# LEDs_PUSH_BUTTONS.net
KiCad netlist of a schematic drawn in Altium Designer
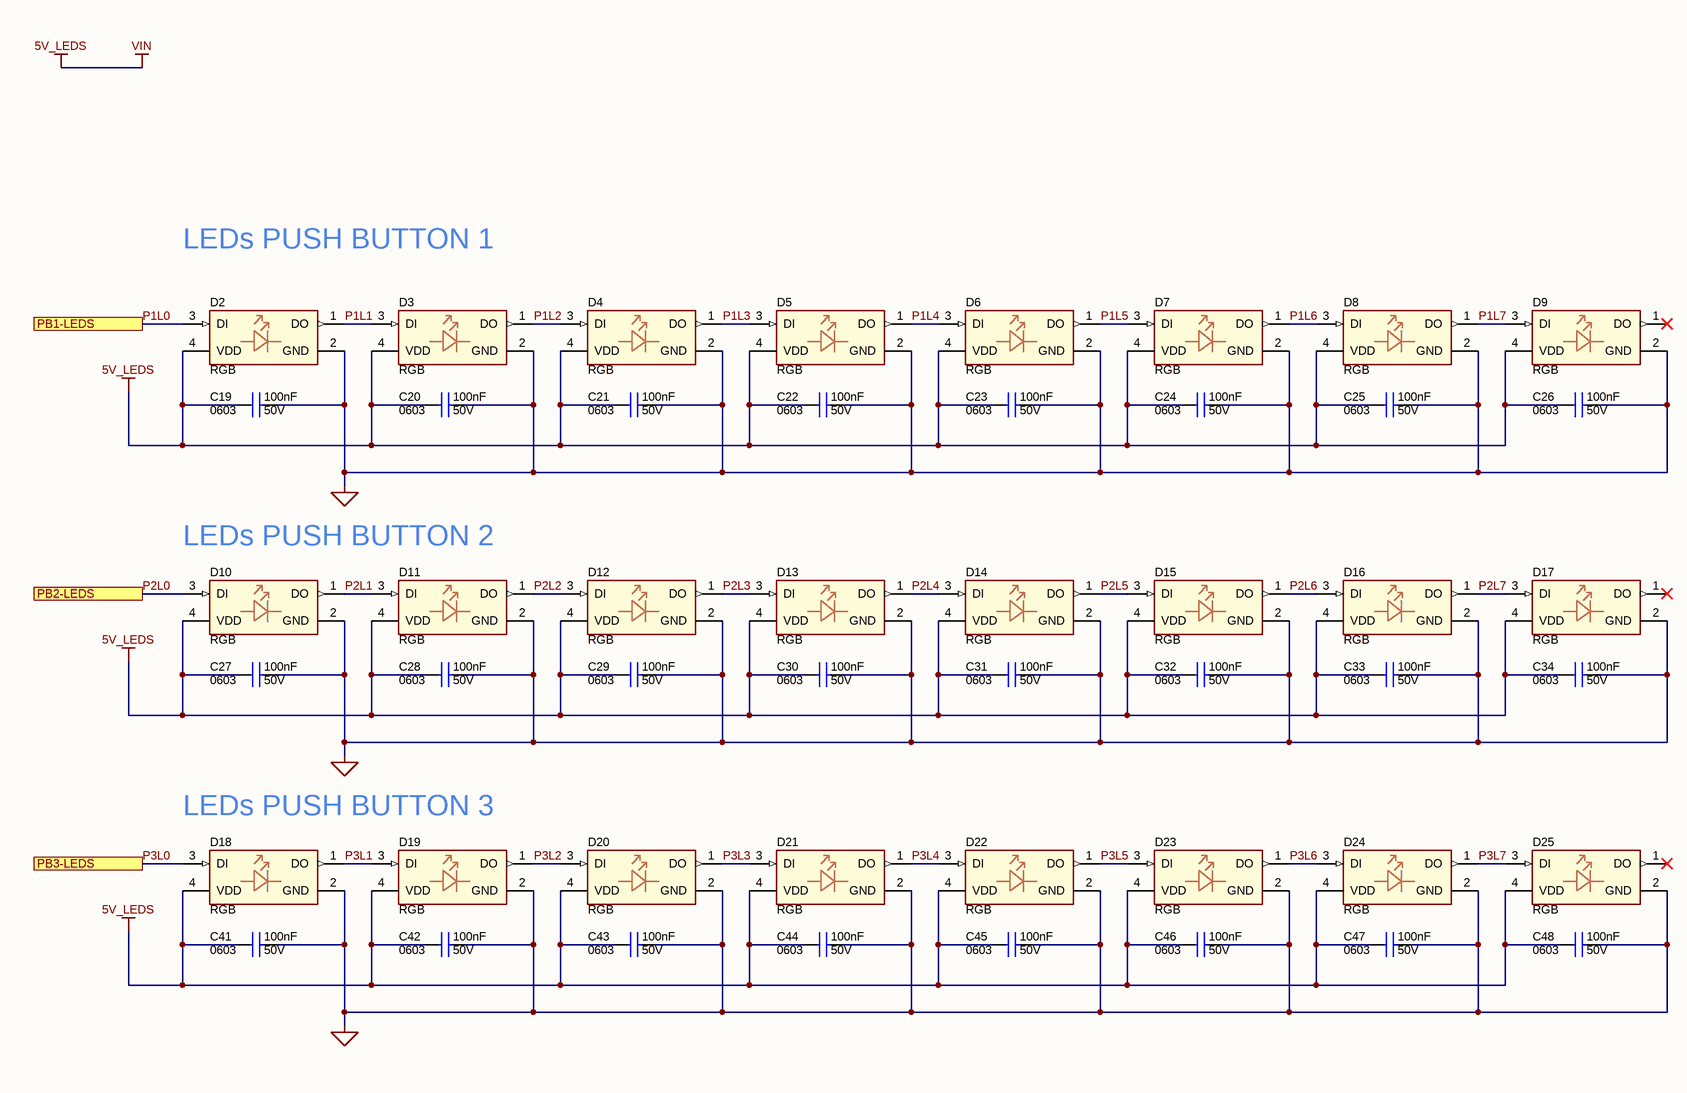
[diagram p0: LEDs PUSH BUTTONS.SchDoc]

(export (version "E")
  (design (tool "Eeschema 10.0.6"))
  (components
    (comp (ref "C19")
      (value "100nF")
      (footprint "CAPC0603X37L")
      (description "CAPACITOR 100 nF 0603 X7R 50V 10%")
      (fields
        (field (name "VOLTAGE") "50V")
        (field (name "MANUFACTURER 1 PART NUMBER") "C0603C104K5RACTU")
        (field (name "TOLERANCE") "10%")
        (field (name "CASE/PACKAGE") "0603")
        (field (name "COMMENT DESIGNER") "can be substituted same values other manufacturer")
      )
      (libsource (lib "EDATRON Solutions GmbH") (part "C"))
    )
    (comp (ref "C20")
      (value "100nF")
      (footprint "CAPC0603X37L")
      (description "CAPACITOR 100 nF 0603 X7R 50V 10%")
      (fields
        (field (name "VOLTAGE") "50V")
        (field (name "MANUFACTURER 1 PART NUMBER") "C0603C104K5RACTU")
        (field (name "TOLERANCE") "10%")
        (field (name "CASE/PACKAGE") "0603")
        (field (name "COMMENT DESIGNER") "can be substituted same values other manufacturer")
      )
      (libsource (lib "EDATRON Solutions GmbH") (part "C"))
    )
    (comp (ref "C21")
      (value "100nF")
      (footprint "CAPC0603X37L")
      (description "CAPACITOR 100 nF 0603 X7R 50V 10%")
      (fields
        (field (name "VOLTAGE") "50V")
        (field (name "MANUFACTURER 1 PART NUMBER") "C0603C104K5RACTU")
        (field (name "TOLERANCE") "10%")
        (field (name "CASE/PACKAGE") "0603")
        (field (name "COMMENT DESIGNER") "can be substituted same values other manufacturer")
      )
      (libsource (lib "EDATRON Solutions GmbH") (part "C"))
    )
    (comp (ref "C22")
      (value "100nF")
      (footprint "CAPC0603X37L")
      (description "CAPACITOR 100 nF 0603 X7R 50V 10%")
      (fields
        (field (name "VOLTAGE") "50V")
        (field (name "MANUFACTURER 1 PART NUMBER") "C0603C104K5RACTU")
        (field (name "TOLERANCE") "10%")
        (field (name "CASE/PACKAGE") "0603")
        (field (name "COMMENT DESIGNER") "can be substituted same values other manufacturer")
      )
      (libsource (lib "EDATRON Solutions GmbH") (part "C"))
    )
    (comp (ref "C23")
      (value "100nF")
      (footprint "CAPC0603X37L")
      (description "CAPACITOR 100 nF 0603 X7R 50V 10%")
      (fields
        (field (name "VOLTAGE") "50V")
        (field (name "MANUFACTURER 1 PART NUMBER") "C0603C104K5RACTU")
        (field (name "TOLERANCE") "10%")
        (field (name "CASE/PACKAGE") "0603")
        (field (name "COMMENT DESIGNER") "can be substituted same values other manufacturer")
      )
      (libsource (lib "EDATRON Solutions GmbH") (part "C"))
    )
    (comp (ref "C24")
      (value "100nF")
      (footprint "CAPC0603X37L")
      (description "CAPACITOR 100 nF 0603 X7R 50V 10%")
      (fields
        (field (name "VOLTAGE") "50V")
        (field (name "MANUFACTURER 1 PART NUMBER") "C0603C104K5RACTU")
        (field (name "TOLERANCE") "10%")
        (field (name "CASE/PACKAGE") "0603")
        (field (name "COMMENT DESIGNER") "can be substituted same values other manufacturer")
      )
      (libsource (lib "EDATRON Solutions GmbH") (part "C"))
    )
    (comp (ref "C25")
      (value "100nF")
      (footprint "CAPC0603X37L")
      (description "CAPACITOR 100 nF 0603 X7R 50V 10%")
      (fields
        (field (name "VOLTAGE") "50V")
        (field (name "MANUFACTURER 1 PART NUMBER") "C0603C104K5RACTU")
        (field (name "TOLERANCE") "10%")
        (field (name "CASE/PACKAGE") "0603")
        (field (name "COMMENT DESIGNER") "can be substituted same values other manufacturer")
      )
      (libsource (lib "EDATRON Solutions GmbH") (part "C"))
    )
    (comp (ref "C26")
      (value "100nF")
      (footprint "CAPC0603X37L")
      (description "CAPACITOR 100 nF 0603 X7R 50V 10%")
      (fields
        (field (name "VOLTAGE") "50V")
        (field (name "MANUFACTURER 1 PART NUMBER") "C0603C104K5RACTU")
        (field (name "TOLERANCE") "10%")
        (field (name "CASE/PACKAGE") "0603")
        (field (name "COMMENT DESIGNER") "can be substituted same values other manufacturer")
      )
      (libsource (lib "EDATRON Solutions GmbH") (part "C"))
    )
    (comp (ref "C27")
      (value "100nF")
      (footprint "CAPC0603X37L")
      (description "CAPACITOR 100 nF 0603 X7R 50V 10%")
      (fields
        (field (name "VOLTAGE") "50V")
        (field (name "MANUFACTURER 1 PART NUMBER") "C0603C104K5RACTU")
        (field (name "TOLERANCE") "10%")
        (field (name "CASE/PACKAGE") "0603")
        (field (name "COMMENT DESIGNER") "can be substituted same values other manufacturer")
      )
      (libsource (lib "EDATRON Solutions GmbH") (part "C"))
    )
    (comp (ref "C28")
      (value "100nF")
      (footprint "CAPC0603X37L")
      (description "CAPACITOR 100 nF 0603 X7R 50V 10%")
      (fields
        (field (name "VOLTAGE") "50V")
        (field (name "MANUFACTURER 1 PART NUMBER") "C0603C104K5RACTU")
        (field (name "TOLERANCE") "10%")
        (field (name "CASE/PACKAGE") "0603")
        (field (name "COMMENT DESIGNER") "can be substituted same values other manufacturer")
      )
      (libsource (lib "EDATRON Solutions GmbH") (part "C"))
    )
    (comp (ref "C29")
      (value "100nF")
      (footprint "CAPC0603X37L")
      (description "CAPACITOR 100 nF 0603 X7R 50V 10%")
      (fields
        (field (name "VOLTAGE") "50V")
        (field (name "MANUFACTURER 1 PART NUMBER") "C0603C104K5RACTU")
        (field (name "TOLERANCE") "10%")
        (field (name "CASE/PACKAGE") "0603")
        (field (name "COMMENT DESIGNER") "can be substituted same values other manufacturer")
      )
      (libsource (lib "EDATRON Solutions GmbH") (part "C"))
    )
    (comp (ref "C30")
      (value "100nF")
      (footprint "CAPC0603X37L")
      (description "CAPACITOR 100 nF 0603 X7R 50V 10%")
      (fields
        (field (name "VOLTAGE") "50V")
        (field (name "MANUFACTURER 1 PART NUMBER") "C0603C104K5RACTU")
        (field (name "TOLERANCE") "10%")
        (field (name "CASE/PACKAGE") "0603")
        (field (name "COMMENT DESIGNER") "can be substituted same values other manufacturer")
      )
      (libsource (lib "EDATRON Solutions GmbH") (part "C"))
    )
    (comp (ref "C31")
      (value "100nF")
      (footprint "CAPC0603X37L")
      (description "CAPACITOR 100 nF 0603 X7R 50V 10%")
      (fields
        (field (name "VOLTAGE") "50V")
        (field (name "MANUFACTURER 1 PART NUMBER") "C0603C104K5RACTU")
        (field (name "TOLERANCE") "10%")
        (field (name "CASE/PACKAGE") "0603")
        (field (name "COMMENT DESIGNER") "can be substituted same values other manufacturer")
      )
      (libsource (lib "EDATRON Solutions GmbH") (part "C"))
    )
    (comp (ref "C32")
      (value "100nF")
      (footprint "CAPC0603X37L")
      (description "CAPACITOR 100 nF 0603 X7R 50V 10%")
      (fields
        (field (name "VOLTAGE") "50V")
        (field (name "MANUFACTURER 1 PART NUMBER") "C0603C104K5RACTU")
        (field (name "TOLERANCE") "10%")
        (field (name "CASE/PACKAGE") "0603")
        (field (name "COMMENT DESIGNER") "can be substituted same values other manufacturer")
      )
      (libsource (lib "EDATRON Solutions GmbH") (part "C"))
    )
    (comp (ref "C33")
      (value "100nF")
      (footprint "CAPC0603X37L")
      (description "CAPACITOR 100 nF 0603 X7R 50V 10%")
      (fields
        (field (name "VOLTAGE") "50V")
        (field (name "MANUFACTURER 1 PART NUMBER") "C0603C104K5RACTU")
        (field (name "TOLERANCE") "10%")
        (field (name "CASE/PACKAGE") "0603")
        (field (name "COMMENT DESIGNER") "can be substituted same values other manufacturer")
      )
      (libsource (lib "EDATRON Solutions GmbH") (part "C"))
    )
    (comp (ref "C34")
      (value "100nF")
      (footprint "CAPC0603X37L")
      (description "CAPACITOR 100 nF 0603 X7R 50V 10%")
      (fields
        (field (name "VOLTAGE") "50V")
        (field (name "MANUFACTURER 1 PART NUMBER") "C0603C104K5RACTU")
        (field (name "TOLERANCE") "10%")
        (field (name "CASE/PACKAGE") "0603")
        (field (name "COMMENT DESIGNER") "can be substituted same values other manufacturer")
      )
      (libsource (lib "EDATRON Solutions GmbH") (part "C"))
    )
    (comp (ref "C41")
      (value "100nF")
      (footprint "CAPC0603X37L")
      (description "CAPACITOR 100 nF 0603 X7R 50V 10%")
      (fields
        (field (name "VOLTAGE") "50V")
        (field (name "MANUFACTURER 1 PART NUMBER") "C0603C104K5RACTU")
        (field (name "TOLERANCE") "10%")
        (field (name "CASE/PACKAGE") "0603")
        (field (name "COMMENT DESIGNER") "can be substituted same values other manufacturer")
      )
      (libsource (lib "EDATRON Solutions GmbH") (part "C"))
    )
    (comp (ref "C42")
      (value "100nF")
      (footprint "CAPC0603X37L")
      (description "CAPACITOR 100 nF 0603 X7R 50V 10%")
      (fields
        (field (name "VOLTAGE") "50V")
        (field (name "MANUFACTURER 1 PART NUMBER") "C0603C104K5RACTU")
        (field (name "TOLERANCE") "10%")
        (field (name "CASE/PACKAGE") "0603")
        (field (name "COMMENT DESIGNER") "can be substituted same values other manufacturer")
      )
      (libsource (lib "EDATRON Solutions GmbH") (part "C"))
    )
    (comp (ref "C43")
      (value "100nF")
      (footprint "CAPC0603X37L")
      (description "CAPACITOR 100 nF 0603 X7R 50V 10%")
      (fields
        (field (name "VOLTAGE") "50V")
        (field (name "MANUFACTURER 1 PART NUMBER") "C0603C104K5RACTU")
        (field (name "TOLERANCE") "10%")
        (field (name "CASE/PACKAGE") "0603")
        (field (name "COMMENT DESIGNER") "can be substituted same values other manufacturer")
      )
      (libsource (lib "EDATRON Solutions GmbH") (part "C"))
    )
    (comp (ref "C44")
      (value "100nF")
      (footprint "CAPC0603X37L")
      (description "CAPACITOR 100 nF 0603 X7R 50V 10%")
      (fields
        (field (name "VOLTAGE") "50V")
        (field (name "MANUFACTURER 1 PART NUMBER") "C0603C104K5RACTU")
        (field (name "TOLERANCE") "10%")
        (field (name "CASE/PACKAGE") "0603")
        (field (name "COMMENT DESIGNER") "can be substituted same values other manufacturer")
      )
      (libsource (lib "EDATRON Solutions GmbH") (part "C"))
    )
    (comp (ref "C45")
      (value "100nF")
      (footprint "CAPC0603X37L")
      (description "CAPACITOR 100 nF 0603 X7R 50V 10%")
      (fields
        (field (name "VOLTAGE") "50V")
        (field (name "MANUFACTURER 1 PART NUMBER") "C0603C104K5RACTU")
        (field (name "TOLERANCE") "10%")
        (field (name "CASE/PACKAGE") "0603")
        (field (name "COMMENT DESIGNER") "can be substituted same values other manufacturer")
      )
      (libsource (lib "EDATRON Solutions GmbH") (part "C"))
    )
    (comp (ref "C46")
      (value "100nF")
      (footprint "CAPC0603X37L")
      (description "CAPACITOR 100 nF 0603 X7R 50V 10%")
      (fields
        (field (name "VOLTAGE") "50V")
        (field (name "MANUFACTURER 1 PART NUMBER") "C0603C104K5RACTU")
        (field (name "TOLERANCE") "10%")
        (field (name "CASE/PACKAGE") "0603")
        (field (name "COMMENT DESIGNER") "can be substituted same values other manufacturer")
      )
      (libsource (lib "EDATRON Solutions GmbH") (part "C"))
    )
    (comp (ref "C47")
      (value "100nF")
      (footprint "CAPC0603X37L")
      (description "CAPACITOR 100 nF 0603 X7R 50V 10%")
      (fields
        (field (name "VOLTAGE") "50V")
        (field (name "MANUFACTURER 1 PART NUMBER") "C0603C104K5RACTU")
        (field (name "TOLERANCE") "10%")
        (field (name "CASE/PACKAGE") "0603")
        (field (name "COMMENT DESIGNER") "can be substituted same values other manufacturer")
      )
      (libsource (lib "EDATRON Solutions GmbH") (part "C"))
    )
    (comp (ref "C48")
      (value "100nF")
      (footprint "CAPC0603X37L")
      (description "CAPACITOR 100 nF 0603 X7R 50V 10%")
      (fields
        (field (name "VOLTAGE") "50V")
        (field (name "MANUFACTURER 1 PART NUMBER") "C0603C104K5RACTU")
        (field (name "TOLERANCE") "10%")
        (field (name "CASE/PACKAGE") "0603")
        (field (name "COMMENT DESIGNER") "can be substituted same values other manufacturer")
      )
      (libsource (lib "EDATRON Solutions GmbH") (part "C"))
    )
    (comp (ref "D2")
      (value "WS2812B-2020")
      (footprint "WS2812B-2020")
      (description "LED")
      (fields (field (name "COLOR") "RGB") (field (name "VOLTAGE") "5V"))
      (libsource (lib "EDATRON Solutions GmbH") (part "RGB-LED (Built-in IC)"))
    )
    (comp (ref "D3")
      (value "WS2812B-2020")
      (footprint "WS2812B-2020")
      (description "LED")
      (fields (field (name "COLOR") "RGB") (field (name "VOLTAGE") "5V"))
      (libsource (lib "EDATRON Solutions GmbH") (part "RGB-LED (Built-in IC)"))
    )
    (comp (ref "D4")
      (value "WS2812B-2020")
      (footprint "WS2812B-2020")
      (description "LED")
      (fields (field (name "COLOR") "RGB") (field (name "VOLTAGE") "5V"))
      (libsource (lib "EDATRON Solutions GmbH") (part "RGB-LED (Built-in IC)"))
    )
    (comp (ref "D5")
      (value "WS2812B-2020")
      (footprint "WS2812B-2020")
      (description "LED")
      (fields (field (name "COLOR") "RGB") (field (name "VOLTAGE") "5V"))
      (libsource (lib "EDATRON Solutions GmbH") (part "RGB-LED (Built-in IC)"))
    )
    (comp (ref "D6")
      (value "WS2812B-2020")
      (footprint "WS2812B-2020")
      (description "LED")
      (fields (field (name "COLOR") "RGB") (field (name "VOLTAGE") "5V"))
      (libsource (lib "EDATRON Solutions GmbH") (part "RGB-LED (Built-in IC)"))
    )
    (comp (ref "D7")
      (value "WS2812B-2020")
      (footprint "WS2812B-2020")
      (description "LED")
      (fields (field (name "COLOR") "RGB") (field (name "VOLTAGE") "5V"))
      (libsource (lib "EDATRON Solutions GmbH") (part "RGB-LED (Built-in IC)"))
    )
    (comp (ref "D8")
      (value "WS2812B-2020")
      (footprint "WS2812B-2020")
      (description "LED")
      (fields (field (name "COLOR") "RGB") (field (name "VOLTAGE") "5V"))
      (libsource (lib "EDATRON Solutions GmbH") (part "RGB-LED (Built-in IC)"))
    )
    (comp (ref "D9")
      (value "WS2812B-2020")
      (footprint "WS2812B-2020")
      (description "LED")
      (fields (field (name "COLOR") "RGB") (field (name "VOLTAGE") "5V"))
      (libsource (lib "EDATRON Solutions GmbH") (part "RGB-LED (Built-in IC)"))
    )
    (comp (ref "D10")
      (value "WS2812B-2020")
      (footprint "WS2812B-2020")
      (description "LED")
      (fields (field (name "COLOR") "RGB") (field (name "VOLTAGE") "5V"))
      (libsource (lib "EDATRON Solutions GmbH") (part "RGB-LED (Built-in IC)"))
    )
    (comp (ref "D11")
      (value "WS2812B-2020")
      (footprint "WS2812B-2020")
      (description "LED")
      (fields (field (name "COLOR") "RGB") (field (name "VOLTAGE") "5V"))
      (libsource (lib "EDATRON Solutions GmbH") (part "RGB-LED (Built-in IC)"))
    )
    (comp (ref "D12")
      (value "WS2812B-2020")
      (footprint "WS2812B-2020")
      (description "LED")
      (fields (field (name "COLOR") "RGB") (field (name "VOLTAGE") "5V"))
      (libsource (lib "EDATRON Solutions GmbH") (part "RGB-LED (Built-in IC)"))
    )
    (comp (ref "D13")
      (value "WS2812B-2020")
      (footprint "WS2812B-2020")
      (description "LED")
      (fields (field (name "COLOR") "RGB") (field (name "VOLTAGE") "5V"))
      (libsource (lib "EDATRON Solutions GmbH") (part "RGB-LED (Built-in IC)"))
    )
    (comp (ref "D14")
      (value "WS2812B-2020")
      (footprint "WS2812B-2020")
      (description "LED")
      (fields (field (name "COLOR") "RGB") (field (name "VOLTAGE") "5V"))
      (libsource (lib "EDATRON Solutions GmbH") (part "RGB-LED (Built-in IC)"))
    )
    (comp (ref "D15")
      (value "WS2812B-2020")
      (footprint "WS2812B-2020")
      (description "LED")
      (fields (field (name "COLOR") "RGB") (field (name "VOLTAGE") "5V"))
      (libsource (lib "EDATRON Solutions GmbH") (part "RGB-LED (Built-in IC)"))
    )
    (comp (ref "D16")
      (value "WS2812B-2020")
      (footprint "WS2812B-2020")
      (description "LED")
      (fields (field (name "COLOR") "RGB") (field (name "VOLTAGE") "5V"))
      (libsource (lib "EDATRON Solutions GmbH") (part "RGB-LED (Built-in IC)"))
    )
    (comp (ref "D17")
      (value "WS2812B-2020")
      (footprint "WS2812B-2020")
      (description "LED")
      (fields (field (name "COLOR") "RGB") (field (name "VOLTAGE") "5V"))
      (libsource (lib "EDATRON Solutions GmbH") (part "RGB-LED (Built-in IC)"))
    )
    (comp (ref "D18")
      (value "WS2812B-2020")
      (footprint "WS2812B-2020")
      (description "LED")
      (fields (field (name "COLOR") "RGB") (field (name "VOLTAGE") "5V"))
      (libsource (lib "EDATRON Solutions GmbH") (part "RGB-LED (Built-in IC)"))
    )
    (comp (ref "D19")
      (value "WS2812B-2020")
      (footprint "WS2812B-2020")
      (description "LED")
      (fields (field (name "COLOR") "RGB") (field (name "VOLTAGE") "5V"))
      (libsource (lib "EDATRON Solutions GmbH") (part "RGB-LED (Built-in IC)"))
    )
    (comp (ref "D20")
      (value "WS2812B-2020")
      (footprint "WS2812B-2020")
      (description "LED")
      (fields (field (name "COLOR") "RGB") (field (name "VOLTAGE") "5V"))
      (libsource (lib "EDATRON Solutions GmbH") (part "RGB-LED (Built-in IC)"))
    )
    (comp (ref "D21")
      (value "WS2812B-2020")
      (footprint "WS2812B-2020")
      (description "LED")
      (fields (field (name "COLOR") "RGB") (field (name "VOLTAGE") "5V"))
      (libsource (lib "EDATRON Solutions GmbH") (part "RGB-LED (Built-in IC)"))
    )
    (comp (ref "D22")
      (value "WS2812B-2020")
      (footprint "WS2812B-2020")
      (description "LED")
      (fields (field (name "COLOR") "RGB") (field (name "VOLTAGE") "5V"))
      (libsource (lib "EDATRON Solutions GmbH") (part "RGB-LED (Built-in IC)"))
    )
    (comp (ref "D23")
      (value "WS2812B-2020")
      (footprint "WS2812B-2020")
      (description "LED")
      (fields (field (name "COLOR") "RGB") (field (name "VOLTAGE") "5V"))
      (libsource (lib "EDATRON Solutions GmbH") (part "RGB-LED (Built-in IC)"))
    )
    (comp (ref "D24")
      (value "WS2812B-2020")
      (footprint "WS2812B-2020")
      (description "LED")
      (fields (field (name "COLOR") "RGB") (field (name "VOLTAGE") "5V"))
      (libsource (lib "EDATRON Solutions GmbH") (part "RGB-LED (Built-in IC)"))
    )
    (comp (ref "D25")
      (value "WS2812B-2020")
      (footprint "WS2812B-2020")
      (description "LED")
      (fields (field (name "COLOR") "RGB") (field (name "VOLTAGE") "5V"))
      (libsource (lib "EDATRON Solutions GmbH") (part "RGB-LED (Built-in IC)"))
    )
  )
  (nets
    (net (code "1") (name "/P1L0") (class "Default")
      (node (ref "D2") (pin "3") (pinfunction "DI_3") (pintype "input"))
    )
    (net (code "2") (name "/P1L1") (class "Default")
      (node (ref "D2") (pin "1") (pinfunction "DO_1") (pintype "output"))
      (node (ref "D3") (pin "3") (pinfunction "DI_3") (pintype "input"))
    )
    (net (code "3") (name "/P1L2") (class "Default")
      (node (ref "D3") (pin "1") (pinfunction "DO_1") (pintype "output"))
      (node (ref "D4") (pin "3") (pinfunction "DI_3") (pintype "input"))
    )
    (net (code "4") (name "/P1L3") (class "Default")
      (node (ref "D4") (pin "1") (pinfunction "DO_1") (pintype "output"))
      (node (ref "D5") (pin "3") (pinfunction "DI_3") (pintype "input"))
    )
    (net (code "5") (name "/P1L4") (class "Default")
      (node (ref "D5") (pin "1") (pinfunction "DO_1") (pintype "output"))
      (node (ref "D6") (pin "3") (pinfunction "DI_3") (pintype "input"))
    )
    (net (code "6") (name "/P1L5") (class "Default")
      (node (ref "D6") (pin "1") (pinfunction "DO_1") (pintype "output"))
      (node (ref "D7") (pin "3") (pinfunction "DI_3") (pintype "input"))
    )
    (net (code "7") (name "/P1L6") (class "Default")
      (node (ref "D7") (pin "1") (pinfunction "DO_1") (pintype "output"))
      (node (ref "D8") (pin "3") (pinfunction "DI_3") (pintype "input"))
    )
    (net (code "8") (name "/P1L7") (class "Default")
      (node (ref "D8") (pin "1") (pinfunction "DO_1") (pintype "output"))
      (node (ref "D9") (pin "3") (pinfunction "DI_3") (pintype "input"))
    )
    (net (code "9") (name "/P2L0") (class "Default")
      (node (ref "D10") (pin "3") (pinfunction "DI_3") (pintype "input"))
    )
    (net (code "10") (name "/P2L1") (class "Default")
      (node (ref "D10") (pin "1") (pinfunction "DO_1") (pintype "output"))
      (node (ref "D11") (pin "3") (pinfunction "DI_3") (pintype "input"))
    )
    (net (code "11") (name "/P2L2") (class "Default")
      (node (ref "D11") (pin "1") (pinfunction "DO_1") (pintype "output"))
      (node (ref "D12") (pin "3") (pinfunction "DI_3") (pintype "input"))
    )
    (net (code "12") (name "/P2L3") (class "Default")
      (node (ref "D12") (pin "1") (pinfunction "DO_1") (pintype "output"))
      (node (ref "D13") (pin "3") (pinfunction "DI_3") (pintype "input"))
    )
    (net (code "13") (name "/P2L4") (class "Default")
      (node (ref "D13") (pin "1") (pinfunction "DO_1") (pintype "output"))
      (node (ref "D14") (pin "3") (pinfunction "DI_3") (pintype "input"))
    )
    (net (code "14") (name "/P2L5") (class "Default")
      (node (ref "D14") (pin "1") (pinfunction "DO_1") (pintype "output"))
      (node (ref "D15") (pin "3") (pinfunction "DI_3") (pintype "input"))
    )
    (net (code "15") (name "/P2L6") (class "Default")
      (node (ref "D15") (pin "1") (pinfunction "DO_1") (pintype "output"))
      (node (ref "D16") (pin "3") (pinfunction "DI_3") (pintype "input"))
    )
    (net (code "16") (name "/P2L7") (class "Default")
      (node (ref "D16") (pin "1") (pinfunction "DO_1") (pintype "output"))
      (node (ref "D17") (pin "3") (pinfunction "DI_3") (pintype "input"))
    )
    (net (code "17") (name "/P3L0") (class "Default")
      (node (ref "D18") (pin "3") (pinfunction "DI_3") (pintype "input"))
    )
    (net (code "18") (name "/P3L1") (class "Default")
      (node (ref "D18") (pin "1") (pinfunction "DO_1") (pintype "output"))
      (node (ref "D19") (pin "3") (pinfunction "DI_3") (pintype "input"))
    )
    (net (code "19") (name "/P3L2") (class "Default")
      (node (ref "D19") (pin "1") (pinfunction "DO_1") (pintype "output"))
      (node (ref "D20") (pin "3") (pinfunction "DI_3") (pintype "input"))
    )
    (net (code "20") (name "/P3L3") (class "Default")
      (node (ref "D20") (pin "1") (pinfunction "DO_1") (pintype "output"))
      (node (ref "D21") (pin "3") (pinfunction "DI_3") (pintype "input"))
    )
    (net (code "21") (name "/P3L4") (class "Default")
      (node (ref "D21") (pin "1") (pinfunction "DO_1") (pintype "output"))
      (node (ref "D22") (pin "3") (pinfunction "DI_3") (pintype "input"))
    )
    (net (code "22") (name "/P3L5") (class "Default")
      (node (ref "D22") (pin "1") (pinfunction "DO_1") (pintype "output"))
      (node (ref "D23") (pin "3") (pinfunction "DI_3") (pintype "input"))
    )
    (net (code "23") (name "/P3L6") (class "Default")
      (node (ref "D23") (pin "1") (pinfunction "DO_1") (pintype "output"))
      (node (ref "D24") (pin "3") (pinfunction "DI_3") (pintype "input"))
    )
    (net (code "24") (name "/P3L7") (class "Default")
      (node (ref "D24") (pin "1") (pinfunction "DO_1") (pintype "output"))
      (node (ref "D25") (pin "3") (pinfunction "DI_3") (pintype "input"))
    )
    (net (code "25") (name "5V_LEDS") (class "Default")
      (node (ref "C19") (pin "1") (pinfunction "1_1") (pintype "passive"))
      (node (ref "C20") (pin "1") (pinfunction "1_1") (pintype "passive"))
      (node (ref "C21") (pin "1") (pinfunction "1_1") (pintype "passive"))
      (node (ref "C22") (pin "1") (pinfunction "1_1") (pintype "passive"))
      (node (ref "C23") (pin "1") (pinfunction "1_1") (pintype "passive"))
      (node (ref "C24") (pin "1") (pinfunction "1_1") (pintype "passive"))
      (node (ref "C25") (pin "1") (pinfunction "1_1") (pintype "passive"))
      (node (ref "C26") (pin "1") (pinfunction "1_1") (pintype "passive"))
      (node (ref "C27") (pin "1") (pinfunction "1_1") (pintype "passive"))
      (node (ref "C28") (pin "1") (pinfunction "1_1") (pintype "passive"))
      (node (ref "C29") (pin "1") (pinfunction "1_1") (pintype "passive"))
      (node (ref "C30") (pin "1") (pinfunction "1_1") (pintype "passive"))
      (node (ref "C31") (pin "1") (pinfunction "1_1") (pintype "passive"))
      (node (ref "C32") (pin "1") (pinfunction "1_1") (pintype "passive"))
      (node (ref "C33") (pin "1") (pinfunction "1_1") (pintype "passive"))
      (node (ref "C34") (pin "1") (pinfunction "1_1") (pintype "passive"))
      (node (ref "C41") (pin "1") (pinfunction "1_1") (pintype "passive"))
      (node (ref "C42") (pin "1") (pinfunction "1_1") (pintype "passive"))
      (node (ref "C43") (pin "1") (pinfunction "1_1") (pintype "passive"))
      (node (ref "C44") (pin "1") (pinfunction "1_1") (pintype "passive"))
      (node (ref "C45") (pin "1") (pinfunction "1_1") (pintype "passive"))
      (node (ref "C46") (pin "1") (pinfunction "1_1") (pintype "passive"))
      (node (ref "C47") (pin "1") (pinfunction "1_1") (pintype "passive"))
      (node (ref "C48") (pin "1") (pinfunction "1_1") (pintype "passive"))
      (node (ref "D10") (pin "4") (pinfunction "VDD_4") (pintype "passive"))
      (node (ref "D11") (pin "4") (pinfunction "VDD_4") (pintype "passive"))
      (node (ref "D12") (pin "4") (pinfunction "VDD_4") (pintype "passive"))
      (node (ref "D13") (pin "4") (pinfunction "VDD_4") (pintype "passive"))
      (node (ref "D14") (pin "4") (pinfunction "VDD_4") (pintype "passive"))
      (node (ref "D15") (pin "4") (pinfunction "VDD_4") (pintype "passive"))
      (node (ref "D16") (pin "4") (pinfunction "VDD_4") (pintype "passive"))
      (node (ref "D17") (pin "4") (pinfunction "VDD_4") (pintype "passive"))
      (node (ref "D18") (pin "4") (pinfunction "VDD_4") (pintype "passive"))
      (node (ref "D19") (pin "4") (pinfunction "VDD_4") (pintype "passive"))
      (node (ref "D2") (pin "4") (pinfunction "VDD_4") (pintype "passive"))
      (node (ref "D20") (pin "4") (pinfunction "VDD_4") (pintype "passive"))
      (node (ref "D21") (pin "4") (pinfunction "VDD_4") (pintype "passive"))
      (node (ref "D22") (pin "4") (pinfunction "VDD_4") (pintype "passive"))
      (node (ref "D23") (pin "4") (pinfunction "VDD_4") (pintype "passive"))
      (node (ref "D24") (pin "4") (pinfunction "VDD_4") (pintype "passive"))
      (node (ref "D25") (pin "4") (pinfunction "VDD_4") (pintype "passive"))
      (node (ref "D3") (pin "4") (pinfunction "VDD_4") (pintype "passive"))
      (node (ref "D4") (pin "4") (pinfunction "VDD_4") (pintype "passive"))
      (node (ref "D5") (pin "4") (pinfunction "VDD_4") (pintype "passive"))
      (node (ref "D6") (pin "4") (pinfunction "VDD_4") (pintype "passive"))
      (node (ref "D7") (pin "4") (pinfunction "VDD_4") (pintype "passive"))
      (node (ref "D8") (pin "4") (pinfunction "VDD_4") (pintype "passive"))
      (node (ref "D9") (pin "4") (pinfunction "VDD_4") (pintype "passive"))
    )
    (net (code "26") (name "GND") (class "Default")
      (node (ref "C19") (pin "2") (pinfunction "2_2") (pintype "passive"))
      (node (ref "C20") (pin "2") (pinfunction "2_2") (pintype "passive"))
      (node (ref "C21") (pin "2") (pinfunction "2_2") (pintype "passive"))
      (node (ref "C22") (pin "2") (pinfunction "2_2") (pintype "passive"))
      (node (ref "C23") (pin "2") (pinfunction "2_2") (pintype "passive"))
      (node (ref "C24") (pin "2") (pinfunction "2_2") (pintype "passive"))
      (node (ref "C25") (pin "2") (pinfunction "2_2") (pintype "passive"))
      (node (ref "C26") (pin "2") (pinfunction "2_2") (pintype "passive"))
      (node (ref "C27") (pin "2") (pinfunction "2_2") (pintype "passive"))
      (node (ref "C28") (pin "2") (pinfunction "2_2") (pintype "passive"))
      (node (ref "C29") (pin "2") (pinfunction "2_2") (pintype "passive"))
      (node (ref "C30") (pin "2") (pinfunction "2_2") (pintype "passive"))
      (node (ref "C31") (pin "2") (pinfunction "2_2") (pintype "passive"))
      (node (ref "C32") (pin "2") (pinfunction "2_2") (pintype "passive"))
      (node (ref "C33") (pin "2") (pinfunction "2_2") (pintype "passive"))
      (node (ref "C34") (pin "2") (pinfunction "2_2") (pintype "passive"))
      (node (ref "C41") (pin "2") (pinfunction "2_2") (pintype "passive"))
      (node (ref "C42") (pin "2") (pinfunction "2_2") (pintype "passive"))
      (node (ref "C43") (pin "2") (pinfunction "2_2") (pintype "passive"))
      (node (ref "C44") (pin "2") (pinfunction "2_2") (pintype "passive"))
      (node (ref "C45") (pin "2") (pinfunction "2_2") (pintype "passive"))
      (node (ref "C46") (pin "2") (pinfunction "2_2") (pintype "passive"))
      (node (ref "C47") (pin "2") (pinfunction "2_2") (pintype "passive"))
      (node (ref "C48") (pin "2") (pinfunction "2_2") (pintype "passive"))
      (node (ref "D10") (pin "2") (pinfunction "GND_2") (pintype "passive"))
      (node (ref "D11") (pin "2") (pinfunction "GND_2") (pintype "passive"))
      (node (ref "D12") (pin "2") (pinfunction "GND_2") (pintype "passive"))
      (node (ref "D13") (pin "2") (pinfunction "GND_2") (pintype "passive"))
      (node (ref "D14") (pin "2") (pinfunction "GND_2") (pintype "passive"))
      (node (ref "D15") (pin "2") (pinfunction "GND_2") (pintype "passive"))
      (node (ref "D16") (pin "2") (pinfunction "GND_2") (pintype "passive"))
      (node (ref "D17") (pin "2") (pinfunction "GND_2") (pintype "passive"))
      (node (ref "D18") (pin "2") (pinfunction "GND_2") (pintype "passive"))
      (node (ref "D19") (pin "2") (pinfunction "GND_2") (pintype "passive"))
      (node (ref "D2") (pin "2") (pinfunction "GND_2") (pintype "passive"))
      (node (ref "D20") (pin "2") (pinfunction "GND_2") (pintype "passive"))
      (node (ref "D21") (pin "2") (pinfunction "GND_2") (pintype "passive"))
      (node (ref "D22") (pin "2") (pinfunction "GND_2") (pintype "passive"))
      (node (ref "D23") (pin "2") (pinfunction "GND_2") (pintype "passive"))
      (node (ref "D24") (pin "2") (pinfunction "GND_2") (pintype "passive"))
      (node (ref "D25") (pin "2") (pinfunction "GND_2") (pintype "passive"))
      (node (ref "D3") (pin "2") (pinfunction "GND_2") (pintype "passive"))
      (node (ref "D4") (pin "2") (pinfunction "GND_2") (pintype "passive"))
      (node (ref "D5") (pin "2") (pinfunction "GND_2") (pintype "passive"))
      (node (ref "D6") (pin "2") (pinfunction "GND_2") (pintype "passive"))
      (node (ref "D7") (pin "2") (pinfunction "GND_2") (pintype "passive"))
      (node (ref "D8") (pin "2") (pinfunction "GND_2") (pintype "passive"))
      (node (ref "D9") (pin "2") (pinfunction "GND_2") (pintype "passive"))
    )
    (net (code "27") (name "unconnected-(D9-DO-Pad1)") (class "Default")
      (node (ref "D9") (pin "1") (pinfunction "DO_1") (pintype "output+no_connect"))
    )
    (net (code "28") (name "unconnected-(D17-DO-Pad1)") (class "Default")
      (node (ref "D17") (pin "1") (pinfunction "DO_1") (pintype "output+no_connect"))
    )
    (net (code "29") (name "unconnected-(D25-DO-Pad1)") (class "Default")
      (node (ref "D25") (pin "1") (pinfunction "DO_1") (pintype "output+no_connect"))
    )
  )
)
